# SCH_REV1_3_2024-02-19.net
KiCad netlist of a schematic drawn in EasyEDA
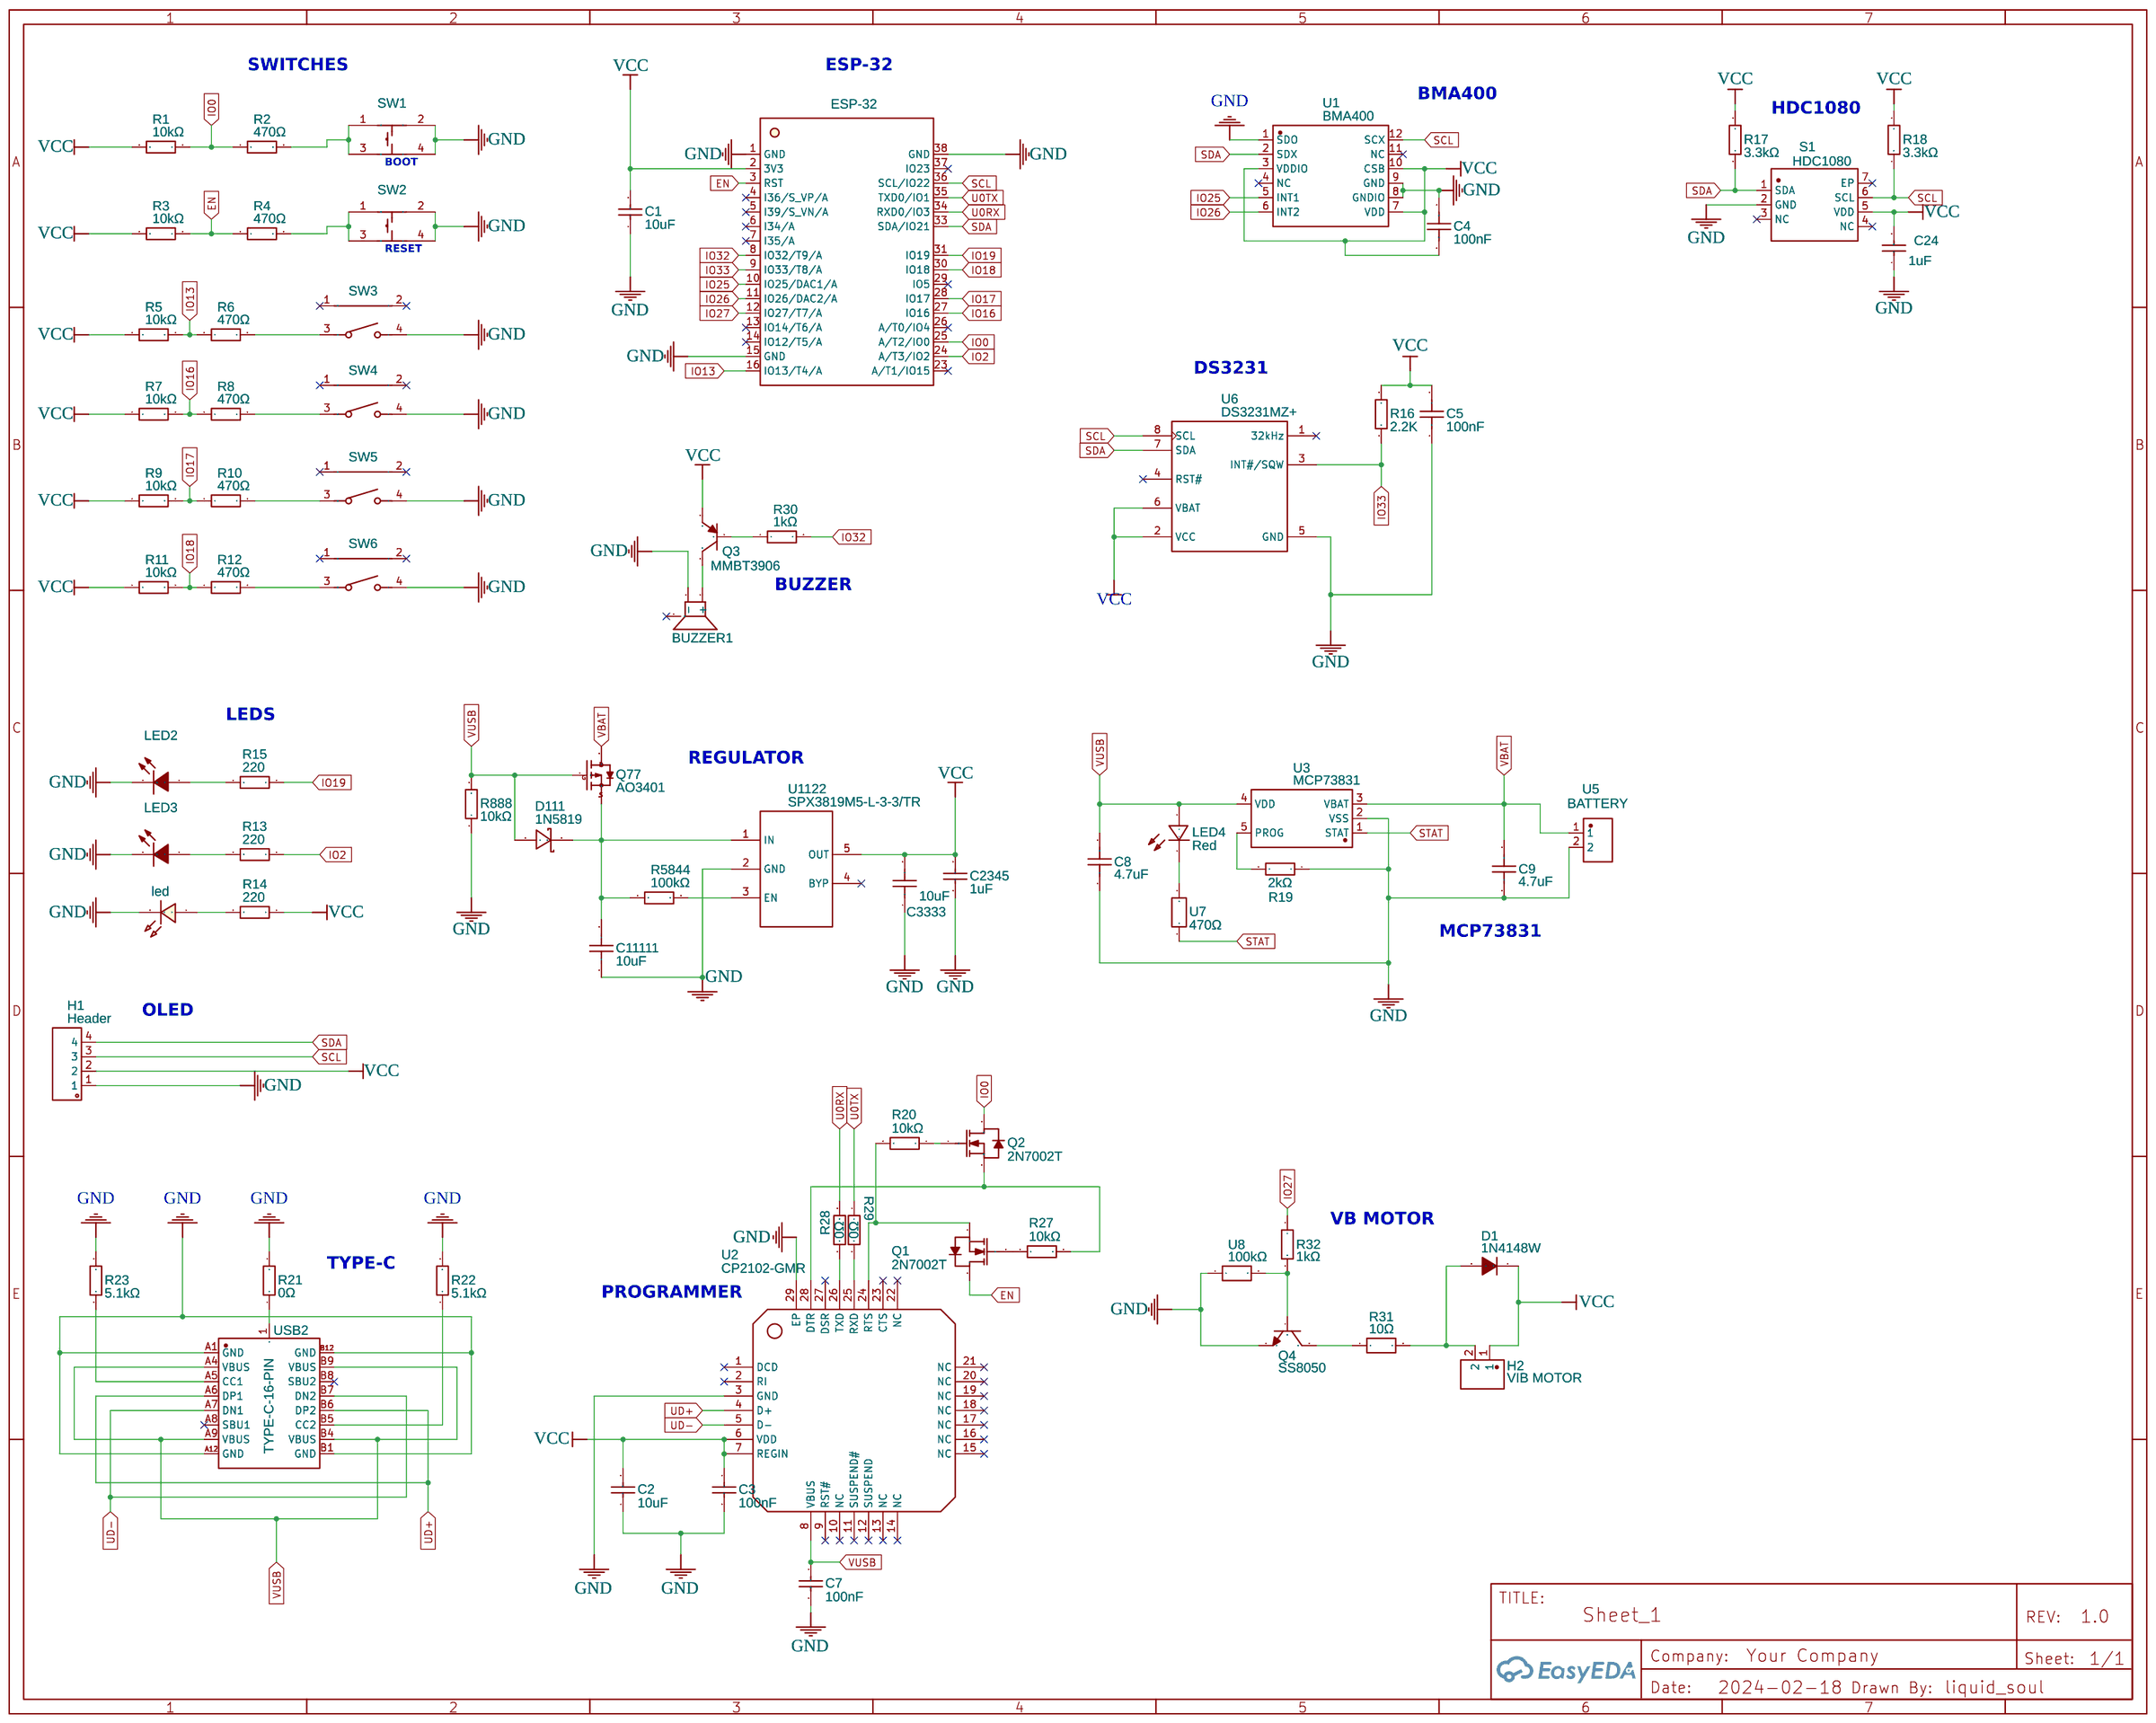
[diagram p0: schematic sheet]

(export (version "E")
  (design (tool "Eeschema 10.0.6"))
  (components
    (comp (ref "BUZZER1")
      (value "4000Hz")
      (fields (field (name "Manufacturer Part") "MLT-5030") (field (name "Manufacturer") "华能"))
      (libsource (lib "") (part "MLT-5030"))
    )
    (comp (ref "C1")
      (value "10uF")
      (fields (field (name "Manufacturer Part") "0603F106M160NT") (field (name "Manufacturer") "FH"))
      (libsource (lib "") (part "0603F106M160NT"))
    )
    (comp (ref "C2")
      (value "10uF")
      (fields (field (name "Manufacturer Part") "0603F106M160NT") (field (name "Manufacturer") "FH"))
      (libsource (lib "") (part "0603F106M160NT"))
    )
    (comp (ref "C3")
      (value "100nF")
      (fields
        (field (name "Manufacturer Part") "FN18X104K500PBG")
        (field (name "Manufacturer") "Prosperity Dielectrics")
      )
      (libsource (lib "") (part "FN18X104K500PBG"))
    )
    (comp (ref "C4")
      (value "100nF")
      (fields (field (name "Manufacturer Part") "06033C104K4T2A") (field (name "Manufacturer") "Kyocera AVX"))
      (libsource (lib "") (part "06033C104K4T2A"))
    )
    (comp (ref "C5")
      (value "100nF")
      (fields (field (name "Manufacturer Part") "06033C104K4T2A") (field (name "Manufacturer") "Kyocera AVX"))
      (libsource (lib "") (part "06033C104K4T2A_1"))
    )
    (comp (ref "C7")
      (value "100nF")
      (fields
        (field (name "Manufacturer Part") "FN18X104K500PBG")
        (field (name "Manufacturer") "Prosperity Dielectrics")
      )
      (libsource (lib "") (part "FN18X104K500PBG"))
    )
    (comp (ref "C8")
      (value "4.7uF")
      (fields
        (field (name "Manufacturer Part") "CC0603KRX5R8BB475")
        (field (name "Manufacturer") "YAGEO(国巨)")
      )
      (libsource (lib "") (part "CC0603KRX5R8BB475"))
    )
    (comp (ref "C9")
      (value "4.7uF")
      (fields
        (field (name "Manufacturer Part") "CC0603KRX5R8BB475")
        (field (name "Manufacturer") "YAGEO(国巨)")
      )
      (libsource (lib "") (part "CC0603KRX5R8BB475"))
    )
    (comp (ref "C24")
      (value "1uF")
      (fields (field (name "Manufacturer Part") "0603B105K250NT") (field (name "Manufacturer") "FH"))
      (libsource (lib "") (part "0603B105K250NT"))
    )
    (comp (ref "C2345")
      (value "1uF")
      (fields (field (name "Manufacturer Part") "0603B105K250NT") (field (name "Manufacturer") "FH"))
      (libsource (lib "") (part "0603B105K250NT"))
    )
    (comp (ref "C3333")
      (value "10uF")
      (fields
        (field (name "Manufacturer Part") "0603X106M250NT")
        (field (name "Manufacturer") "FH(Guangdong Fenghua Advanced Tech)")
      )
      (libsource (lib "") (part "0603X106M250NT"))
    )
    (comp (ref "C11111")
      (value "10uF")
      (fields
        (field (name "Manufacturer Part") "0603X106M250NT")
        (field (name "Manufacturer") "FH(Guangdong Fenghua Advanced Tech)")
      )
      (libsource (lib "") (part "0603X106M250NT"))
    )
    (comp (ref "D1")
      (value "1N4148W")
      (fields (field (name "Manufacturer") "MDD"))
      (libsource (lib "") (part "1N4148W-C84367"))
    )
    (comp (ref "D111")
      (value "1N5819")
      (fields
        (field (name "Manufacturer Part") "1N5819W")
        (field (name "Manufacturer") "Shandong Jingdao Microelectronics")
      )
      (libsource (lib "") (part "1N5819W"))
    )
    (comp (ref "H1")
      (value "Header")
      (fields
        (field (name "Manufacturer Part") "Headers  Pins 1*4P")
        (field (name "Manufacturer") "ReliaPro")
      )
      (libsource (lib "") (part "Header-Male-2.54_1x4_C59481"))
    )
    (comp (ref "H2")
      (value "VIB MOTOR")
      (fields (field (name "Manufacturer Part") "77311-118-02LF") (field (name "Manufacturer") "Amphenol"))
      (libsource (lib "") (part "77311-118-02LF"))
    )
    (comp (ref "LED1")
      (value "led")
      (fields
        (field (name "Manufacturer Part") "19-217/R6C-AL1M2VY/3T")
        (field (name "Manufacturer") "EVERLIGHT(台湾亿光)")
      )
      (libsource (lib "") (part "LED-0603_R"))
    )
    (comp (ref "LED2")
      (value "D-B060306B1-KS2")
      (fields (field (name "Manufacturer Part") "D-060306B1") (field (name "Manufacturer") "ARKLED(方舟)"))
      (libsource (lib "") (part "D-B060306B1-KS2"))
    )
    (comp (ref "LED3")
      (value "D-B060306B1-KS2")
      (fields (field (name "Manufacturer Part") "D-060306B1") (field (name "Manufacturer") "ARKLED(方舟)"))
      (libsource (lib "") (part "D-B060306B1-KS2"))
    )
    (comp (ref "LED4")
      (value "Red")
      (fields
        (field (name "Manufacturer Part") "E6Q0603URAC1UDA")
        (field (name "Manufacturer") "ekinglux(亿晶源)")
      )
      (libsource (lib "") (part "E6Q0603URAC1UDA"))
    )
    (comp (ref "Q1")
      (value "2N7002T")
      (fields (field (name "Manufacturer Part") "K2N7002T-7-F") (field (name "Manufacturer") "KUU"))
      (libsource (lib "") (part "K2N7002T-7-F"))
    )
    (comp (ref "Q2")
      (value "2N7002T")
      (fields (field (name "Manufacturer Part") "K2N7002T-7-F") (field (name "Manufacturer") "KUU"))
      (libsource (lib "") (part "K2N7002T-7-F_1"))
    )
    (comp (ref "Q3")
      (value "MMBT3906")
      (fields (field (name "Manufacturer") "YONGYUTAI(永裕泰)"))
      (libsource (lib "") (part "MMBT3906_C2891809"))
    )
    (comp (ref "Q4")
      (value "SS8050")
      (fields (field (name "Manufacturer") "JSMSEMI(杰盛微)"))
      (libsource (lib "") (part "SS8050_C916392"))
    )
    (comp (ref "Q77")
      (value "AO3401")
      (fields (field (name "Manufacturer") "Hottech"))
      (libsource (lib "") (part "AO3401"))
    )
    (comp (ref "R1")
      (value "10kΩ")
      (fields (field (name "Manufacturer Part") "SY0603JN10KP") (field (name "Manufacturer") "SANYEAR"))
      (libsource (lib "") (part "SY0603JN10KP"))
    )
    (comp (ref "R2")
      (value "470Ω")
      (fields
        (field (name "Manufacturer Part") "QR0603F470RP05")
        (field (name "Manufacturer") "Ever Ohms Tech")
      )
      (libsource (lib "") (part "QR0603F470RP05"))
    )
    (comp (ref "R3")
      (value "10kΩ")
      (fields (field (name "Manufacturer Part") "SY0603JN10KP") (field (name "Manufacturer") "SANYEAR"))
      (libsource (lib "") (part "SY0603JN10KP"))
    )
    (comp (ref "R4")
      (value "470Ω")
      (fields
        (field (name "Manufacturer Part") "QR0603F470RP05")
        (field (name "Manufacturer") "Ever Ohms Tech")
      )
      (libsource (lib "") (part "QR0603F470RP05"))
    )
    (comp (ref "R5")
      (value "10kΩ")
      (fields (field (name "Manufacturer Part") "SY0603JN10KP") (field (name "Manufacturer") "SANYEAR"))
      (libsource (lib "") (part "SY0603JN10KP"))
    )
    (comp (ref "R6")
      (value "470Ω")
      (fields
        (field (name "Manufacturer Part") "QR0603F470RP05")
        (field (name "Manufacturer") "Ever Ohms Tech")
      )
      (libsource (lib "") (part "QR0603F470RP05"))
    )
    (comp (ref "R7")
      (value "10kΩ")
      (fields (field (name "Manufacturer Part") "SY0603JN10KP") (field (name "Manufacturer") "SANYEAR"))
      (libsource (lib "") (part "SY0603JN10KP"))
    )
    (comp (ref "R8")
      (value "470Ω")
      (fields
        (field (name "Manufacturer Part") "QR0603F470RP05")
        (field (name "Manufacturer") "Ever Ohms Tech")
      )
      (libsource (lib "") (part "QR0603F470RP05"))
    )
    (comp (ref "R9")
      (value "10kΩ")
      (fields (field (name "Manufacturer Part") "SY0603JN10KP") (field (name "Manufacturer") "SANYEAR"))
      (libsource (lib "") (part "SY0603JN10KP"))
    )
    (comp (ref "R10")
      (value "470Ω")
      (fields
        (field (name "Manufacturer Part") "QR0603F470RP05")
        (field (name "Manufacturer") "Ever Ohms Tech")
      )
      (libsource (lib "") (part "QR0603F470RP05"))
    )
    (comp (ref "R11")
      (value "10kΩ")
      (fields (field (name "Manufacturer Part") "SY0603JN10KP") (field (name "Manufacturer") "SANYEAR"))
      (libsource (lib "") (part "SY0603JN10KP"))
    )
    (comp (ref "R12")
      (value "470Ω")
      (fields
        (field (name "Manufacturer Part") "QR0603F470RP05")
        (field (name "Manufacturer") "Ever Ohms Tech")
      )
      (libsource (lib "") (part "QR0603F470RP05"))
    )
    (comp (ref "R13")
      (value "220")
      (fields (field (name "Manufacturer Part") "AF0603FR-07220RL") (field (name "Manufacturer") "YAGEO"))
      (libsource (lib "") (part "AF0603FR-07220RL"))
    )
    (comp (ref "R14")
      (value "220")
      (fields (field (name "Manufacturer Part") "AF0603FR-07220RL") (field (name "Manufacturer") "YAGEO"))
      (libsource (lib "") (part "AF0603FR-07220RL"))
    )
    (comp (ref "R15")
      (value "220")
      (fields (field (name "Manufacturer Part") "AF0603FR-07220RL") (field (name "Manufacturer") "YAGEO"))
      (libsource (lib "") (part "AF0603FR-07220RL"))
    )
    (comp (ref "R16")
      (value "2.2K")
      (fields (field (name "Manufacturer Part") "RMC06032.2K1%N") (field (name "Manufacturer") "Tyohm(幸亚电阻)"))
      (libsource (lib "") (part "RMC06032.2K1%N"))
    )
    (comp (ref "R17")
      (value "3.3kΩ")
      (fields (field (name "Manufacturer Part") "RMC06033.3K5%N") (field (name "Manufacturer") "Tyohm(幸亚电阻)"))
      (libsource (lib "") (part "RMC06033.3K5%N"))
    )
    (comp (ref "R18")
      (value "3.3kΩ")
      (fields (field (name "Manufacturer Part") "RMC06033.3K5%N") (field (name "Manufacturer") "Tyohm(幸亚电阻)"))
      (libsource (lib "") (part "RMC06033.3K5%N"))
    )
    (comp (ref "R19")
      (value "2kΩ")
      (fields
        (field (name "Manufacturer Part") "RMC 0603 2K J N")
        (field (name "Manufacturer") "Tyohm(幸亚电阻)")
      )
      (libsource (lib "") (part "RMC06032K5%N"))
    )
    (comp (ref "R20")
      (value "10kΩ")
      (fields (field (name "Manufacturer Part") "SY0603JN10KP") (field (name "Manufacturer") "SANYEAR"))
      (libsource (lib "") (part "SY0603JN10KP_1"))
    )
    (comp (ref "R21")
      (value "0Ω")
      (fields
        (field (name "Manufacturer Part") "ETCR0603F0000K9")
        (field (name "Manufacturer") "ResistorToday")
      )
      (libsource (lib "") (part "ETCR0603F0000K9_1"))
    )
    (comp (ref "R22")
      (value "5.1kΩ")
      (fields (field (name "Manufacturer Part") "RMC06035.1K1%N") (field (name "Manufacturer") "Tyohm"))
      (libsource (lib "") (part "RMC06035.1K1%N"))
    )
    (comp (ref "R23")
      (value "5.1kΩ")
      (fields (field (name "Manufacturer Part") "RMC06035.1K1%N") (field (name "Manufacturer") "Tyohm"))
      (libsource (lib "") (part "RMC06035.1K1%N"))
    )
    (comp (ref "R27")
      (value "10kΩ")
      (fields (field (name "Manufacturer Part") "SY0603JN10KP") (field (name "Manufacturer") "SANYEAR"))
      (libsource (lib "") (part "SY0603JN10KP_1"))
    )
    (comp (ref "R28")
      (value "0Ω")
      (fields
        (field (name "Manufacturer Part") "ETCR0603F0000K9")
        (field (name "Manufacturer") "ResistorToday")
      )
      (libsource (lib "") (part "ETCR0603F0000K9_1"))
    )
    (comp (ref "R29")
      (value "0Ω")
      (fields
        (field (name "Manufacturer Part") "ETCR0603F0000K9")
        (field (name "Manufacturer") "ResistorToday")
      )
      (libsource (lib "") (part "ETCR0603F0000K9"))
    )
    (comp (ref "R30")
      (value "1kΩ")
      (fields
        (field (name "Manufacturer Part") "0603WAF1001T5E")
        (field (name "Manufacturer") "UNI-ROYAL(厚声)")
      )
      (libsource (lib "") (part "0603WAF1001T5E"))
    )
    (comp (ref "R31")
      (value "10Ω")
      (fields (field (name "Manufacturer Part") "CR-03JL7---10R") (field (name "Manufacturer") "Viking(光颉)"))
      (libsource (lib "") (part "CR-03JL7---10R"))
    )
    (comp (ref "R32")
      (value "1kΩ")
      (fields (field (name "Manufacturer Part") "RMC06031K5%N") (field (name "Manufacturer") "Tyohm(幸亚电阻)"))
      (libsource (lib "") (part "RMC06031K5%N"))
    )
    (comp (ref "R888")
      (value "10kΩ")
      (fields (field (name "Manufacturer Part") "RMC060310K1%N") (field (name "Manufacturer") "Tyohm"))
      (libsource (lib "") (part "RMC060310K1%N"))
    )
    (comp (ref "R5844")
      (value "100kΩ")
      (fields (field (name "Manufacturer Part") "RMC0603100K1%N") (field (name "Manufacturer") "Tyohm"))
      (libsource (lib "") (part "RMC0603100K1%N"))
    )
    (comp (ref "S1")
      (value "HDC1080")
      (fields (field (name "Manufacturer Part") "HDC1080DMBR") (field (name "Manufacturer") "TI(德州仪器)"))
      (libsource (lib "") (part "HDC1080DMBR"))
    )
    (comp (ref "SW1")
      (value "SKRPACE010")
      (fields (field (name "Manufacturer") "ALPSALPINE(阿尔卑斯阿尔派)"))
      (libsource (lib "") (part "SKRPACE010"))
    )
    (comp (ref "SW2")
      (value "SKRPACE010")
      (fields (field (name "Manufacturer") "ALPSALPINE(阿尔卑斯阿尔派)"))
      (libsource (lib "") (part "SKRPACE010"))
    )
    (comp (ref "SW3")
      (value "TS24CA")
      (fields (field (name "Manufacturer") "SHOU HAN(首韩)"))
      (libsource (lib "") (part "TS24CA"))
    )
    (comp (ref "SW4")
      (value "TS24CA")
      (fields (field (name "Manufacturer") "SHOU HAN(首韩)"))
      (libsource (lib "") (part "TS24CA"))
    )
    (comp (ref "SW5")
      (value "TS24CA")
      (fields (field (name "Manufacturer") "SHOU HAN(首韩)"))
      (libsource (lib "") (part "TS24CA"))
    )
    (comp (ref "SW6")
      (value "TS24CA")
      (fields (field (name "Manufacturer") "SHOU HAN(首韩)"))
      (libsource (lib "") (part "TS24CA"))
    )
    (comp (ref "U1")
      (value "BMA400")
      (fields (field (name "Manufacturer") "Bosch(博世)"))
      (libsource (lib "") (part "BMA400"))
    )
    (comp (ref "U2")
      (value "CP2102-GMR")
      (fields (field (name "Manufacturer") "SILICON LABS"))
      (libsource (lib "") (part "CP2102-GMR"))
    )
    (comp (ref "U3")
      (value "MCP73831")
      (fields
        (field (name "Manufacturer Part") "MCP73831T-2DCI/OT")
        (field (name "Manufacturer") "MICROCHIP(美国微芯)")
      )
      (libsource (lib "") (part "MCP73831T-2DCI/OT"))
    )
    (comp (ref "U4")
      (value "ESP-32")
      (fields (field (name "Manufacturer Part") "ESP-32S") (field (name "Manufacturer") "Ai-Thinker"))
      (libsource (lib "") (part "安信可ESP-32S"))
    )
    (comp (ref "U5")
      (value "BATTERY")
      (fields
        (field (name "Manufacturer Part") "KH-2.54FH-1X2P-H8.5")
        (field (name "Manufacturer") "kinghelm(金航标)")
      )
      (libsource (lib "") (part "KH-2.54FH-1X2P-H8.5"))
    )
    (comp (ref "U6")
      (value "DS3231MZ+")
      (fields
        (field (name "Manufacturer Part") "DS3231MZ+TRL")
        (field (name "Manufacturer") "ADI(亚德诺)/MAXIM(美信)")
      )
      (libsource (lib "") (part "DS3231MZ+"))
    )
    (comp (ref "U7")
      (value "470Ω")
      (fields (field (name "Manufacturer Part") "SCR0603F470R") (field (name "Manufacturer") "VO(翔胜)"))
      (libsource (lib "") (part "SCR0603F470R"))
    )
    (comp (ref "U8")
      (value "100kΩ")
      (fields (field (name "Manufacturer Part") "SCR0603F100K") (field (name "Manufacturer") "VO(翔胜)"))
      (libsource (lib "") (part "SCR0603F100K"))
    )
    (comp (ref "U1122")
      (value "SPX3819M5-L-3-3/TR")
      (fields (field (name "Manufacturer") "EXAR"))
      (libsource (lib "") (part "SPX3819M5-L-3-3/TR"))
    )
    (comp (ref "USB2")
      (value "TYPE-C-16-PIN")
      (fields
        (field (name "Manufacturer Part") "TYPE-C-2.0-16PIN-SMT-3")
        (field (name "Manufacturer") "CIKI(皓富)")
      )
      (libsource (lib "") (part "TYPE-C-2.0-16PIN-SMT-3"))
    )
  )
  (nets
    (net (code "1") (name "EN") (class "Default")
      (node (ref "Q1") (pin "3") (pinfunction "D_3") (pintype "unspecified"))
      (node (ref "R3") (pin "2") (pinfunction "2_2") (pintype "unspecified"))
      (node (ref "R4") (pin "1") (pinfunction "1_1") (pintype "unspecified"))
      (node (ref "U4") (pin "3") (pinfunction "RST_3") (pintype "unspecified"))
    )
    (net (code "2") (name "GND") (class "Default")
      (node (ref "BUZZER1") (pin "3") (pinfunction "-_3") (pintype "unspecified"))
      (node (ref "C1") (pin "1") (pinfunction "1_1") (pintype "input"))
      (node (ref "C11111") (pin "1") (pinfunction "1_1") (pintype "unspecified"))
      (node (ref "C2") (pin "1") (pinfunction "1_1") (pintype "input"))
      (node (ref "C2345") (pin "1") (pinfunction "1_1") (pintype "input"))
      (node (ref "C24") (pin "1") (pinfunction "1_1") (pintype "input"))
      (node (ref "C3") (pin "2") (pinfunction "2_2") (pintype "input"))
      (node (ref "C3333") (pin "1") (pinfunction "1_1") (pintype "unspecified"))
      (node (ref "C4") (pin "1") (pinfunction "1_1") (pintype "unspecified"))
      (node (ref "C5") (pin "1") (pinfunction "1_1") (pintype "unspecified"))
      (node (ref "C7") (pin "2") (pinfunction "2_2") (pintype "input"))
      (node (ref "C8") (pin "1") (pinfunction "1_1") (pintype "unspecified"))
      (node (ref "C9") (pin "1") (pinfunction "1_1") (pintype "unspecified"))
      (node (ref "H1") (pin "1") (pinfunction "1_1") (pintype "unspecified"))
      (node (ref "LED1") (pin "2") (pinfunction "2_2") (pintype "unspecified"))
      (node (ref "LED2") (pin "1") (pinfunction "1_1") (pintype "unspecified"))
      (node (ref "LED3") (pin "1") (pinfunction "1_1") (pintype "unspecified"))
      (node (ref "Q4") (pin "2") (pinfunction "E_2") (pintype "input"))
      (node (ref "R19") (pin "1") (pinfunction "1_1") (pintype "unspecified"))
      (node (ref "R21") (pin "2") (pinfunction "2_2") (pintype "unspecified"))
      (node (ref "R22") (pin "2") (pinfunction "2_2") (pintype "unspecified"))
      (node (ref "R23") (pin "2") (pinfunction "2_2") (pintype "unspecified"))
      (node (ref "R888") (pin "1") (pinfunction "1_1") (pintype "unspecified"))
      (node (ref "S1") (pin "2") (pinfunction "GND_2") (pintype "unspecified"))
      (node (ref "SW1") (pin "2") (pinfunction "2_2") (pintype "unspecified"))
      (node (ref "SW1") (pin "4") (pinfunction "4_4") (pintype "unspecified"))
      (node (ref "SW2") (pin "2") (pinfunction "2_2") (pintype "unspecified"))
      (node (ref "SW2") (pin "4") (pinfunction "4_4") (pintype "unspecified"))
      (node (ref "SW3") (pin "4") (pinfunction "4_4") (pintype "unspecified"))
      (node (ref "SW4") (pin "4") (pinfunction "4_4") (pintype "unspecified"))
      (node (ref "SW5") (pin "4") (pinfunction "4_4") (pintype "unspecified"))
      (node (ref "SW6") (pin "4") (pinfunction "4_4") (pintype "unspecified"))
      (node (ref "U1") (pin "1") (pinfunction "SDO_1") (pintype "unspecified"))
      (node (ref "U1") (pin "8") (pinfunction "GNDIO_8") (pintype "unspecified"))
      (node (ref "U1") (pin "9") (pinfunction "GND_9") (pintype "unspecified"))
      (node (ref "U1122") (pin "2") (pinfunction "GND_2") (pintype "unspecified"))
      (node (ref "U2") (pin "29") (pinfunction "EP_29") (pintype "unspecified"))
      (node (ref "U2") (pin "3") (pinfunction "GND_3") (pintype "unspecified"))
      (node (ref "U3") (pin "2") (pinfunction "VSS_2") (pintype "unspecified"))
      (node (ref "U4") (pin "1") (pinfunction "GND_1") (pintype "unspecified"))
      (node (ref "U4") (pin "15") (pinfunction "GND_15") (pintype "unspecified"))
      (node (ref "U4") (pin "38") (pinfunction "GND_38") (pintype "unspecified"))
      (node (ref "U5") (pin "2") (pinfunction "2_2") (pintype "unspecified"))
      (node (ref "U6") (pin "5") (pinfunction "GND_5") (pintype "passive"))
      (node (ref "U8") (pin "1") (pinfunction "1_1") (pintype "unspecified"))
      (node (ref "USB2") (pin "A1") (pinfunction "GND_A1") (pintype "unspecified"))
      (node (ref "USB2") (pin "A12") (pinfunction "GND_A12") (pintype "unspecified"))
      (node (ref "USB2") (pin "B1") (pinfunction "GND_B1") (pintype "unspecified"))
      (node (ref "USB2") (pin "B12") (pinfunction "GND_B12") (pintype "unspecified"))
    )
    (net (code "3") (name "IO0") (class "Default")
      (node (ref "Q2") (pin "3") (pinfunction "D_3") (pintype "unspecified"))
      (node (ref "R1") (pin "2") (pinfunction "2_2") (pintype "unspecified"))
      (node (ref "R2") (pin "1") (pinfunction "1_1") (pintype "unspecified"))
      (node (ref "U4") (pin "25") (pinfunction "A/T2/IO0_25") (pintype "unspecified"))
    )
    (net (code "4") (name "IO2") (class "Default")
      (node (ref "R13") (pin "1") (pinfunction "1_1") (pintype "unspecified"))
      (node (ref "U4") (pin "24") (pinfunction "A/T3/IO2_24") (pintype "unspecified"))
    )
    (net (code "5") (name "IO13") (class "Default")
      (node (ref "R5") (pin "2") (pinfunction "2_2") (pintype "unspecified"))
      (node (ref "R6") (pin "1") (pinfunction "1_1") (pintype "unspecified"))
      (node (ref "U4") (pin "16") (pinfunction "IO13/T4/A_16") (pintype "unspecified"))
    )
    (net (code "6") (name "IO16") (class "Default")
      (node (ref "R7") (pin "2") (pinfunction "2_2") (pintype "unspecified"))
      (node (ref "R8") (pin "1") (pinfunction "1_1") (pintype "unspecified"))
      (node (ref "U4") (pin "27") (pinfunction "IO16_27") (pintype "unspecified"))
    )
    (net (code "7") (name "IO17") (class "Default")
      (node (ref "R10") (pin "1") (pinfunction "1_1") (pintype "unspecified"))
      (node (ref "R9") (pin "2") (pinfunction "2_2") (pintype "unspecified"))
      (node (ref "U4") (pin "28") (pinfunction "IO17_28") (pintype "unspecified"))
    )
    (net (code "8") (name "IO18") (class "Default")
      (node (ref "R11") (pin "2") (pinfunction "2_2") (pintype "unspecified"))
      (node (ref "R12") (pin "1") (pinfunction "1_1") (pintype "unspecified"))
      (node (ref "U4") (pin "30") (pinfunction "IO18_30") (pintype "unspecified"))
    )
    (net (code "9") (name "IO19") (class "Default")
      (node (ref "R15") (pin "1") (pinfunction "1_1") (pintype "unspecified"))
      (node (ref "U4") (pin "31") (pinfunction "IO19_31") (pintype "unspecified"))
    )
    (net (code "10") (name "IO25") (class "Default")
      (node (ref "U1") (pin "5") (pinfunction "INT1_5") (pintype "unspecified"))
      (node (ref "U4") (pin "10") (pinfunction "IO25/DAC1/A_10") (pintype "unspecified"))
    )
    (net (code "11") (name "IO26") (class "Default")
      (node (ref "U1") (pin "6") (pinfunction "INT2_6") (pintype "unspecified"))
      (node (ref "U4") (pin "11") (pinfunction "IO26/DAC2/A_11") (pintype "unspecified"))
    )
    (net (code "12") (name "IO27") (class "Default")
      (node (ref "R32") (pin "1") (pinfunction "1_1") (pintype "unspecified"))
      (node (ref "U4") (pin "12") (pinfunction "IO27/T7/A_12") (pintype "unspecified"))
    )
    (net (code "13") (name "IO32") (class "Default")
      (node (ref "R30") (pin "2") (pinfunction "2_2") (pintype "input"))
      (node (ref "U4") (pin "8") (pinfunction "IO32/T9/A_8") (pintype "unspecified"))
    )
    (net (code "14") (name "IO33") (class "Default")
      (node (ref "R16") (pin "1") (pinfunction "1_1") (pintype "unspecified"))
      (node (ref "U4") (pin "9") (pinfunction "IO33/T8/A_9") (pintype "unspecified"))
      (node (ref "U6") (pin "3") (pinfunction "INT#/SQW_3") (pintype "bidirectional"))
    )
    (net (code "15") (name "Net-(BUZZER1-+)") (class "Default")
      (node (ref "BUZZER1") (pin "2") (pinfunction "+_2") (pintype "unspecified"))
      (node (ref "Q3") (pin "3") (pinfunction "C_3") (pintype "input"))
    )
    (net (code "16") (name "Net-(D1-A)") (class "Default")
      (node (ref "D1") (pin "2") (pinfunction "A_2") (pintype "unspecified"))
      (node (ref "H2") (pin "2") (pinfunction "2_2") (pintype "unspecified"))
      (node (ref "R31") (pin "2") (pinfunction "2_2") (pintype "unspecified"))
    )
    (net (code "17") (name "Net-(LED1-Pad1)") (class "Default")
      (node (ref "LED1") (pin "1") (pinfunction "1_1") (pintype "unspecified"))
      (node (ref "R14") (pin "2") (pinfunction "2_2") (pintype "unspecified"))
    )
    (net (code "18") (name "Net-(LED2-Pad2)") (class "Default")
      (node (ref "LED2") (pin "2") (pinfunction "2_2") (pintype "unspecified"))
      (node (ref "R15") (pin "2") (pinfunction "2_2") (pintype "unspecified"))
    )
    (net (code "19") (name "Net-(LED3-Pad2)") (class "Default")
      (node (ref "LED3") (pin "2") (pinfunction "2_2") (pintype "unspecified"))
      (node (ref "R13") (pin "2") (pinfunction "2_2") (pintype "unspecified"))
    )
    (net (code "20") (name "Net-(LED4--)") (class "Default")
      (node (ref "LED4") (pin "1") (pinfunction "-_1") (pintype "unspecified"))
      (node (ref "U7") (pin "2") (pinfunction "2_2") (pintype "unspecified"))
    )
    (net (code "21") (name "Net-(Q1-G)") (class "Default")
      (node (ref "Q1") (pin "1") (pinfunction "G_1") (pintype "unspecified"))
      (node (ref "R27") (pin "2") (pinfunction "2_2") (pintype "unspecified"))
    )
    (net (code "22") (name "Net-(Q1-S)") (class "Default")
      (node (ref "Q1") (pin "2") (pinfunction "S_2") (pintype "unspecified"))
      (node (ref "R20") (pin "2") (pinfunction "2_2") (pintype "unspecified"))
      (node (ref "U2") (pin "24") (pinfunction "RTS_24") (pintype "unspecified"))
    )
    (net (code "23") (name "Net-(Q2-G)") (class "Default")
      (node (ref "Q2") (pin "1") (pinfunction "G_1") (pintype "unspecified"))
      (node (ref "R20") (pin "1") (pinfunction "1_1") (pintype "unspecified"))
    )
    (net (code "24") (name "Net-(Q2-S)") (class "Default")
      (node (ref "Q2") (pin "2") (pinfunction "S_2") (pintype "unspecified"))
      (node (ref "R27") (pin "1") (pinfunction "1_1") (pintype "unspecified"))
      (node (ref "U2") (pin "28") (pinfunction "DTR_28") (pintype "unspecified"))
    )
    (net (code "25") (name "Net-(Q3-B)") (class "Default")
      (node (ref "Q3") (pin "1") (pinfunction "B_1") (pintype "input"))
      (node (ref "R30") (pin "1") (pinfunction "1_1") (pintype "input"))
    )
    (net (code "26") (name "Net-(Q4-B)") (class "Default")
      (node (ref "Q4") (pin "1") (pinfunction "B_1") (pintype "input"))
      (node (ref "R32") (pin "2") (pinfunction "2_2") (pintype "unspecified"))
      (node (ref "U8") (pin "2") (pinfunction "2_2") (pintype "unspecified"))
    )
    (net (code "27") (name "Net-(Q4-C)") (class "Default")
      (node (ref "Q4") (pin "3") (pinfunction "C_3") (pintype "input"))
      (node (ref "R31") (pin "1") (pinfunction "1_1") (pintype "unspecified"))
    )
    (net (code "28") (name "Net-(Q77-S)") (class "Default")
      (node (ref "C11111") (pin "2") (pinfunction "2_2") (pintype "unspecified"))
      (node (ref "D111") (pin "1") (pinfunction "1_1") (pintype "unspecified"))
      (node (ref "Q77") (pin "2") (pinfunction "S_2") (pintype "unspecified"))
      (node (ref "R5844") (pin "1") (pinfunction "1_1") (pintype "unspecified"))
      (node (ref "U1122") (pin "1") (pinfunction "IN_1") (pintype "unspecified"))
    )
    (net (code "29") (name "Net-(R2-Pad2)") (class "Default")
      (node (ref "R2") (pin "2") (pinfunction "2_2") (pintype "unspecified"))
      (node (ref "SW1") (pin "1") (pinfunction "1_1") (pintype "unspecified"))
      (node (ref "SW1") (pin "3") (pinfunction "3_3") (pintype "unspecified"))
    )
    (net (code "30") (name "Net-(R4-Pad2)") (class "Default")
      (node (ref "R4") (pin "2") (pinfunction "2_2") (pintype "unspecified"))
      (node (ref "SW2") (pin "1") (pinfunction "1_1") (pintype "unspecified"))
      (node (ref "SW2") (pin "3") (pinfunction "3_3") (pintype "unspecified"))
    )
    (net (code "31") (name "Net-(R6-Pad2)") (class "Default")
      (node (ref "R6") (pin "2") (pinfunction "2_2") (pintype "unspecified"))
      (node (ref "SW3") (pin "3") (pinfunction "3_3") (pintype "unspecified"))
    )
    (net (code "32") (name "Net-(R8-Pad2)") (class "Default")
      (node (ref "R8") (pin "2") (pinfunction "2_2") (pintype "unspecified"))
      (node (ref "SW4") (pin "3") (pinfunction "3_3") (pintype "unspecified"))
    )
    (net (code "33") (name "Net-(R10-Pad2)") (class "Default")
      (node (ref "R10") (pin "2") (pinfunction "2_2") (pintype "unspecified"))
      (node (ref "SW5") (pin "3") (pinfunction "3_3") (pintype "unspecified"))
    )
    (net (code "34") (name "Net-(R12-Pad2)") (class "Default")
      (node (ref "R12") (pin "2") (pinfunction "2_2") (pintype "unspecified"))
      (node (ref "SW6") (pin "3") (pinfunction "3_3") (pintype "unspecified"))
    )
    (net (code "35") (name "Net-(U2-RXD)") (class "Default")
      (node (ref "R29") (pin "2") (pinfunction "2_2") (pintype "unspecified"))
      (node (ref "U2") (pin "25") (pinfunction "RXD_25") (pintype "unspecified"))
    )
    (net (code "36") (name "Net-(U2-TXD)") (class "Default")
      (node (ref "R28") (pin "1") (pinfunction "1_1") (pintype "unspecified"))
      (node (ref "U2") (pin "26") (pinfunction "TXD_26") (pintype "unspecified"))
    )
    (net (code "37") (name "Net-(U3-PROG)") (class "Default")
      (node (ref "R19") (pin "2") (pinfunction "2_2") (pintype "unspecified"))
      (node (ref "U3") (pin "5") (pinfunction "PROG_5") (pintype "unspecified"))
    )
    (net (code "38") (name "Net-(U1122-EN)") (class "Default")
      (node (ref "R5844") (pin "2") (pinfunction "2_2") (pintype "unspecified"))
      (node (ref "U1122") (pin "3") (pinfunction "EN_3") (pintype "unspecified"))
    )
    (net (code "39") (name "Net-(USB2-CC1)") (class "Default")
      (node (ref "R23") (pin "1") (pinfunction "1_1") (pintype "unspecified"))
      (node (ref "USB2") (pin "A5") (pinfunction "CC1_A5") (pintype "unspecified"))
    )
    (net (code "40") (name "Net-(USB2-CC2)") (class "Default")
      (node (ref "R22") (pin "1") (pinfunction "1_1") (pintype "unspecified"))
      (node (ref "USB2") (pin "B5") (pinfunction "CC2_B5") (pintype "unspecified"))
    )
    (net (code "41") (name "Net-(USB2-EH)") (class "Default")
      (node (ref "R21") (pin "1") (pinfunction "1_1") (pintype "unspecified"))
      (node (ref "USB2") (pin "1") (pinfunction "EH_1") (pintype "unspecified"))
    )
    (net (code "42") (name "SCL") (class "Default")
      (node (ref "H1") (pin "3") (pinfunction "3_3") (pintype "unspecified"))
      (node (ref "R18") (pin "1") (pinfunction "1_1") (pintype "unspecified"))
      (node (ref "S1") (pin "6") (pinfunction "SCL_6") (pintype "unspecified"))
      (node (ref "U1") (pin "12") (pinfunction "SCX_12") (pintype "unspecified"))
      (node (ref "U4") (pin "36") (pinfunction "SCL/IO22_36") (pintype "unspecified"))
      (node (ref "U6") (pin "8") (pinfunction "SCL_8") (pintype "unspecified"))
    )
    (net (code "43") (name "SDA") (class "Default")
      (node (ref "H1") (pin "4") (pinfunction "4_4") (pintype "unspecified"))
      (node (ref "R17") (pin "1") (pinfunction "1_1") (pintype "unspecified"))
      (node (ref "S1") (pin "1") (pinfunction "SDA_1") (pintype "unspecified"))
      (node (ref "U1") (pin "2") (pinfunction "SDX_2") (pintype "unspecified"))
      (node (ref "U4") (pin "33") (pinfunction "SDA/IO21_33") (pintype "unspecified"))
      (node (ref "U6") (pin "7") (pinfunction "SDA_7") (pintype "bidirectional"))
    )
    (net (code "44") (name "STAT") (class "Default")
      (node (ref "U3") (pin "1") (pinfunction "STAT_1") (pintype "unspecified"))
      (node (ref "U7") (pin "1") (pinfunction "1_1") (pintype "unspecified"))
    )
    (net (code "45") (name "U0RX") (class "Default")
      (node (ref "R28") (pin "2") (pinfunction "2_2") (pintype "unspecified"))
      (node (ref "U4") (pin "34") (pinfunction "RXD0/IO3_34") (pintype "unspecified"))
    )
    (net (code "46") (name "U0TX") (class "Default")
      (node (ref "R29") (pin "1") (pinfunction "1_1") (pintype "unspecified"))
      (node (ref "U4") (pin "35") (pinfunction "TXD0/IO1_35") (pintype "unspecified"))
    )
    (net (code "47") (name "UD+") (class "Default")
      (node (ref "U2") (pin "4") (pinfunction "D+_4") (pintype "unspecified"))
      (node (ref "USB2") (pin "A6") (pinfunction "DP1_A6") (pintype "unspecified"))
      (node (ref "USB2") (pin "B6") (pinfunction "DP2_B6") (pintype "unspecified"))
    )
    (net (code "48") (name "UD-") (class "Default")
      (node (ref "U2") (pin "5") (pinfunction "D-_5") (pintype "unspecified"))
      (node (ref "USB2") (pin "A7") (pinfunction "DN1_A7") (pintype "unspecified"))
      (node (ref "USB2") (pin "B7") (pinfunction "DN2_B7") (pintype "unspecified"))
    )
    (net (code "49") (name "VBAT") (class "Default")
      (node (ref "C9") (pin "2") (pinfunction "2_2") (pintype "unspecified"))
      (node (ref "Q77") (pin "3") (pinfunction "D_3") (pintype "unspecified"))
      (node (ref "U3") (pin "3") (pinfunction "VBAT_3") (pintype "unspecified"))
      (node (ref "U5") (pin "1") (pinfunction "1_1") (pintype "unspecified"))
    )
    (net (code "50") (name "VCC") (class "Default")
      (node (ref "C1") (pin "2") (pinfunction "2_2") (pintype "input"))
      (node (ref "C2") (pin "2") (pinfunction "2_2") (pintype "input"))
      (node (ref "C2345") (pin "2") (pinfunction "2_2") (pintype "input"))
      (node (ref "C24") (pin "2") (pinfunction "2_2") (pintype "input"))
      (node (ref "C3") (pin "1") (pinfunction "1_1") (pintype "input"))
      (node (ref "C3333") (pin "2") (pinfunction "2_2") (pintype "unspecified"))
      (node (ref "C4") (pin "2") (pinfunction "2_2") (pintype "unspecified"))
      (node (ref "C5") (pin "2") (pinfunction "2_2") (pintype "unspecified"))
      (node (ref "D1") (pin "1") (pinfunction "C_1") (pintype "unspecified"))
      (node (ref "H1") (pin "2") (pinfunction "2_2") (pintype "unspecified"))
      (node (ref "H2") (pin "1") (pinfunction "1_1") (pintype "unspecified"))
      (node (ref "Q3") (pin "2") (pinfunction "E_2") (pintype "input"))
      (node (ref "R1") (pin "1") (pinfunction "1_1") (pintype "unspecified"))
      (node (ref "R11") (pin "1") (pinfunction "1_1") (pintype "unspecified"))
      (node (ref "R14") (pin "1") (pinfunction "1_1") (pintype "unspecified"))
      (node (ref "R16") (pin "2") (pinfunction "2_2") (pintype "unspecified"))
      (node (ref "R17") (pin "2") (pinfunction "2_2") (pintype "unspecified"))
      (node (ref "R18") (pin "2") (pinfunction "2_2") (pintype "unspecified"))
      (node (ref "R3") (pin "1") (pinfunction "1_1") (pintype "unspecified"))
      (node (ref "R5") (pin "1") (pinfunction "1_1") (pintype "unspecified"))
      (node (ref "R7") (pin "1") (pinfunction "1_1") (pintype "unspecified"))
      (node (ref "R9") (pin "1") (pinfunction "1_1") (pintype "unspecified"))
      (node (ref "S1") (pin "5") (pinfunction "VDD_5") (pintype "unspecified"))
      (node (ref "U1") (pin "10") (pinfunction "CSB_10") (pintype "unspecified"))
      (node (ref "U1") (pin "3") (pinfunction "VDDIO_3") (pintype "unspecified"))
      (node (ref "U1") (pin "7") (pinfunction "VDD_7") (pintype "unspecified"))
      (node (ref "U1122") (pin "5") (pinfunction "OUT_5") (pintype "unspecified"))
      (node (ref "U2") (pin "6") (pinfunction "VDD_6") (pintype "unspecified"))
      (node (ref "U2") (pin "7") (pinfunction "REGIN_7") (pintype "unspecified"))
      (node (ref "U4") (pin "2") (pinfunction "3V3_2") (pintype "unspecified"))
      (node (ref "U6") (pin "2") (pinfunction "VCC_2") (pintype "passive"))
      (node (ref "U6") (pin "6") (pinfunction "VBAT_6") (pintype "passive"))
    )
    (net (code "51") (name "VUSB") (class "Default")
      (node (ref "C7") (pin "1") (pinfunction "1_1") (pintype "input"))
      (node (ref "C8") (pin "2") (pinfunction "2_2") (pintype "unspecified"))
      (node (ref "D111") (pin "2") (pinfunction "2_2") (pintype "unspecified"))
      (node (ref "LED4") (pin "2") (pinfunction "+_2") (pintype "unspecified"))
      (node (ref "Q77") (pin "1") (pinfunction "G_1") (pintype "unspecified"))
      (node (ref "R888") (pin "2") (pinfunction "2_2") (pintype "unspecified"))
      (node (ref "U2") (pin "8") (pinfunction "VBUS_8") (pintype "unspecified"))
      (node (ref "U3") (pin "4") (pinfunction "VDD_4") (pintype "unspecified"))
      (node (ref "USB2") (pin "A4") (pinfunction "VBUS_A4") (pintype "unspecified"))
      (node (ref "USB2") (pin "A9") (pinfunction "VBUS_A9") (pintype "unspecified"))
      (node (ref "USB2") (pin "B4") (pinfunction "VBUS_B4") (pintype "unspecified"))
      (node (ref "USB2") (pin "B9") (pinfunction "VBUS_B9") (pintype "unspecified"))
    )
    (net (code "52") (name "unconnected-(BUZZER1-NC-Pad1)") (class "Default")
      (node (ref "BUZZER1") (pin "1") (pinfunction "NC_1") (pintype "unspecified+no_connect"))
    )
    (net (code "53") (name "unconnected-(S1-EP-Pad7)") (class "Default")
      (node (ref "S1") (pin "7") (pinfunction "EP_7") (pintype "unspecified+no_connect"))
    )
    (net (code "54") (name "unconnected-(S1-NC-Pad3)") (class "Default")
      (node (ref "S1") (pin "3") (pinfunction "NC_3") (pintype "unspecified+no_connect"))
    )
    (net (code "55") (name "unconnected-(S1-NC-Pad4)") (class "Default")
      (node (ref "S1") (pin "4") (pinfunction "NC_4") (pintype "unspecified+no_connect"))
    )
    (net (code "56") (name "unconnected-(SW3-Pad1)") (class "Default")
      (node (ref "SW3") (pin "1") (pinfunction "1_1") (pintype "unspecified+no_connect"))
    )
    (net (code "57") (name "unconnected-(SW3-Pad2)") (class "Default")
      (node (ref "SW3") (pin "2") (pinfunction "2_2") (pintype "unspecified+no_connect"))
    )
    (net (code "58") (name "unconnected-(SW4-Pad1)") (class "Default")
      (node (ref "SW4") (pin "1") (pinfunction "1_1") (pintype "unspecified+no_connect"))
    )
    (net (code "59") (name "unconnected-(SW4-Pad2)") (class "Default")
      (node (ref "SW4") (pin "2") (pinfunction "2_2") (pintype "unspecified+no_connect"))
    )
    (net (code "60") (name "unconnected-(SW5-Pad1)") (class "Default")
      (node (ref "SW5") (pin "1") (pinfunction "1_1") (pintype "unspecified+no_connect"))
    )
    (net (code "61") (name "unconnected-(SW5-Pad2)") (class "Default")
      (node (ref "SW5") (pin "2") (pinfunction "2_2") (pintype "unspecified+no_connect"))
    )
    (net (code "62") (name "unconnected-(SW6-Pad1)") (class "Default")
      (node (ref "SW6") (pin "1") (pinfunction "1_1") (pintype "unspecified+no_connect"))
    )
    (net (code "63") (name "unconnected-(SW6-Pad2)") (class "Default")
      (node (ref "SW6") (pin "2") (pinfunction "2_2") (pintype "unspecified+no_connect"))
    )
    (net (code "64") (name "unconnected-(U1-NC-Pad4)") (class "Default")
      (node (ref "U1") (pin "4") (pinfunction "NC_4") (pintype "unspecified+no_connect"))
    )
    (net (code "65") (name "unconnected-(U1-NC-Pad11)") (class "Default")
      (node (ref "U1") (pin "11") (pinfunction "NC_11") (pintype "unspecified+no_connect"))
    )
    (net (code "66") (name "unconnected-(U2-CTS-Pad23)") (class "Default")
      (node (ref "U2") (pin "23") (pinfunction "CTS_23") (pintype "unspecified+no_connect"))
    )
    (net (code "67") (name "unconnected-(U2-DCD-Pad1)") (class "Default")
      (node (ref "U2") (pin "1") (pinfunction "DCD_1") (pintype "unspecified+no_connect"))
    )
    (net (code "68") (name "unconnected-(U2-DSR-Pad27)") (class "Default")
      (node (ref "U2") (pin "27") (pinfunction "DSR_27") (pintype "unspecified+no_connect"))
    )
    (net (code "69") (name "unconnected-(U2-NC-Pad10)") (class "Default")
      (node (ref "U2") (pin "10") (pinfunction "NC_10") (pintype "unspecified+no_connect"))
    )
    (net (code "70") (name "unconnected-(U2-NC-Pad13)") (class "Default")
      (node (ref "U2") (pin "13") (pinfunction "NC_13") (pintype "unspecified+no_connect"))
    )
    (net (code "71") (name "unconnected-(U2-NC-Pad14)") (class "Default")
      (node (ref "U2") (pin "14") (pinfunction "NC_14") (pintype "unspecified+no_connect"))
    )
    (net (code "72") (name "unconnected-(U2-NC-Pad15)") (class "Default")
      (node (ref "U2") (pin "15") (pinfunction "NC_15") (pintype "unspecified+no_connect"))
    )
    (net (code "73") (name "unconnected-(U2-NC-Pad16)") (class "Default")
      (node (ref "U2") (pin "16") (pinfunction "NC_16") (pintype "unspecified+no_connect"))
    )
    (net (code "74") (name "unconnected-(U2-NC-Pad17)") (class "Default")
      (node (ref "U2") (pin "17") (pinfunction "NC_17") (pintype "unspecified+no_connect"))
    )
    (net (code "75") (name "unconnected-(U2-NC-Pad18)") (class "Default")
      (node (ref "U2") (pin "18") (pinfunction "NC_18") (pintype "unspecified+no_connect"))
    )
    (net (code "76") (name "unconnected-(U2-NC-Pad19)") (class "Default")
      (node (ref "U2") (pin "19") (pinfunction "NC_19") (pintype "unspecified+no_connect"))
    )
    (net (code "77") (name "unconnected-(U2-NC-Pad20)") (class "Default")
      (node (ref "U2") (pin "20") (pinfunction "NC_20") (pintype "unspecified+no_connect"))
    )
    (net (code "78") (name "unconnected-(U2-NC-Pad21)") (class "Default")
      (node (ref "U2") (pin "21") (pinfunction "NC_21") (pintype "unspecified+no_connect"))
    )
    (net (code "79") (name "unconnected-(U2-NC-Pad22)") (class "Default")
      (node (ref "U2") (pin "22") (pinfunction "NC_22") (pintype "unspecified+no_connect"))
    )
    (net (code "80") (name "unconnected-(U2-RI-Pad2)") (class "Default")
      (node (ref "U2") (pin "2") (pinfunction "RI_2") (pintype "unspecified+no_connect"))
    )
    (net (code "81") (name "unconnected-(U2-RST#-Pad9)") (class "Default")
      (node (ref "U2") (pin "9") (pinfunction "RST#_9") (pintype "unspecified+no_connect"))
    )
    (net (code "82") (name "unconnected-(U2-SUSPEND#-Pad11)") (class "Default")
      (node (ref "U2") (pin "11") (pinfunction "SUSPEND#_11") (pintype "unspecified+no_connect"))
    )
    (net (code "83") (name "unconnected-(U2-SUSPEND-Pad12)") (class "Default")
      (node (ref "U2") (pin "12") (pinfunction "SUSPEND_12") (pintype "unspecified+no_connect"))
    )
    (net (code "84") (name "unconnected-(U4-A{slash}T0{slash}IO4-Pad26)") (class "Default")
      (node (ref "U4") (pin "26") (pinfunction "A/T0/IO4_26") (pintype "unspecified+no_connect"))
    )
    (net (code "85") (name "unconnected-(U4-A{slash}T1{slash}IO15-Pad23)") (class "Default")
      (node (ref "U4") (pin "23") (pinfunction "A/T1/IO15_23") (pintype "unspecified+no_connect"))
    )
    (net (code "86") (name "unconnected-(U4-I34{slash}A-Pad6)") (class "Default")
      (node (ref "U4") (pin "6") (pinfunction "I34/A_6") (pintype "unspecified+no_connect"))
    )
    (net (code "87") (name "unconnected-(U4-I35{slash}A-Pad7)") (class "Default")
      (node (ref "U4") (pin "7") (pinfunction "I35/A_7") (pintype "unspecified+no_connect"))
    )
    (net (code "88") (name "unconnected-(U4-I36{slash}S_VP{slash}A-Pad4)") (class "Default")
      (node (ref "U4") (pin "4") (pinfunction "I36/S_VP/A_4") (pintype "unspecified+no_connect"))
    )
    (net (code "89") (name "unconnected-(U4-I39{slash}S_VN{slash}A-Pad5)") (class "Default")
      (node (ref "U4") (pin "5") (pinfunction "I39/S_VN/A_5") (pintype "unspecified+no_connect"))
    )
    (net (code "90") (name "unconnected-(U4-IO5-Pad29)") (class "Default")
      (node (ref "U4") (pin "29") (pinfunction "IO5_29") (pintype "unspecified+no_connect"))
    )
    (net (code "91") (name "unconnected-(U4-IO12{slash}T5{slash}A-Pad14)") (class "Default")
      (node (ref "U4") (pin "14") (pinfunction "IO12/T5/A_14") (pintype "unspecified+no_connect"))
    )
    (net (code "92") (name "unconnected-(U4-IO14{slash}T6{slash}A-Pad13)") (class "Default")
      (node (ref "U4") (pin "13") (pinfunction "IO14/T6/A_13") (pintype "unspecified+no_connect"))
    )
    (net (code "93") (name "unconnected-(U4-IO23-Pad37)") (class "Default")
      (node (ref "U4") (pin "37") (pinfunction "IO23_37") (pintype "unspecified+no_connect"))
    )
    (net (code "94") (name "unconnected-(U6-32kHz-Pad1)") (class "Default")
      (node (ref "U6") (pin "1") (pinfunction "32kHz_1") (pintype "unspecified+no_connect"))
    )
    (net (code "95") (name "unconnected-(U6-RST#-Pad4)") (class "Default")
      (node (ref "U6") (pin "4") (pinfunction "RST#_4") (pintype "bidirectional+no_connect"))
    )
    (net (code "96") (name "unconnected-(U1122-BYP-Pad4)") (class "Default")
      (node (ref "U1122") (pin "4") (pinfunction "BYP_4") (pintype "unspecified+no_connect"))
    )
    (net (code "97") (name "unconnected-(USB2-SBU1-PadA8)") (class "Default")
      (node (ref "USB2") (pin "A8") (pinfunction "SBU1_A8") (pintype "unspecified+no_connect"))
    )
    (net (code "98") (name "unconnected-(USB2-SBU2-PadB8)") (class "Default")
      (node (ref "USB2") (pin "B8") (pinfunction "SBU2_B8") (pintype "unspecified+no_connect"))
    )
  )
)
